# kelvin_ntc_B.net
KiCad netlist of a schematic drawn in EAGLE
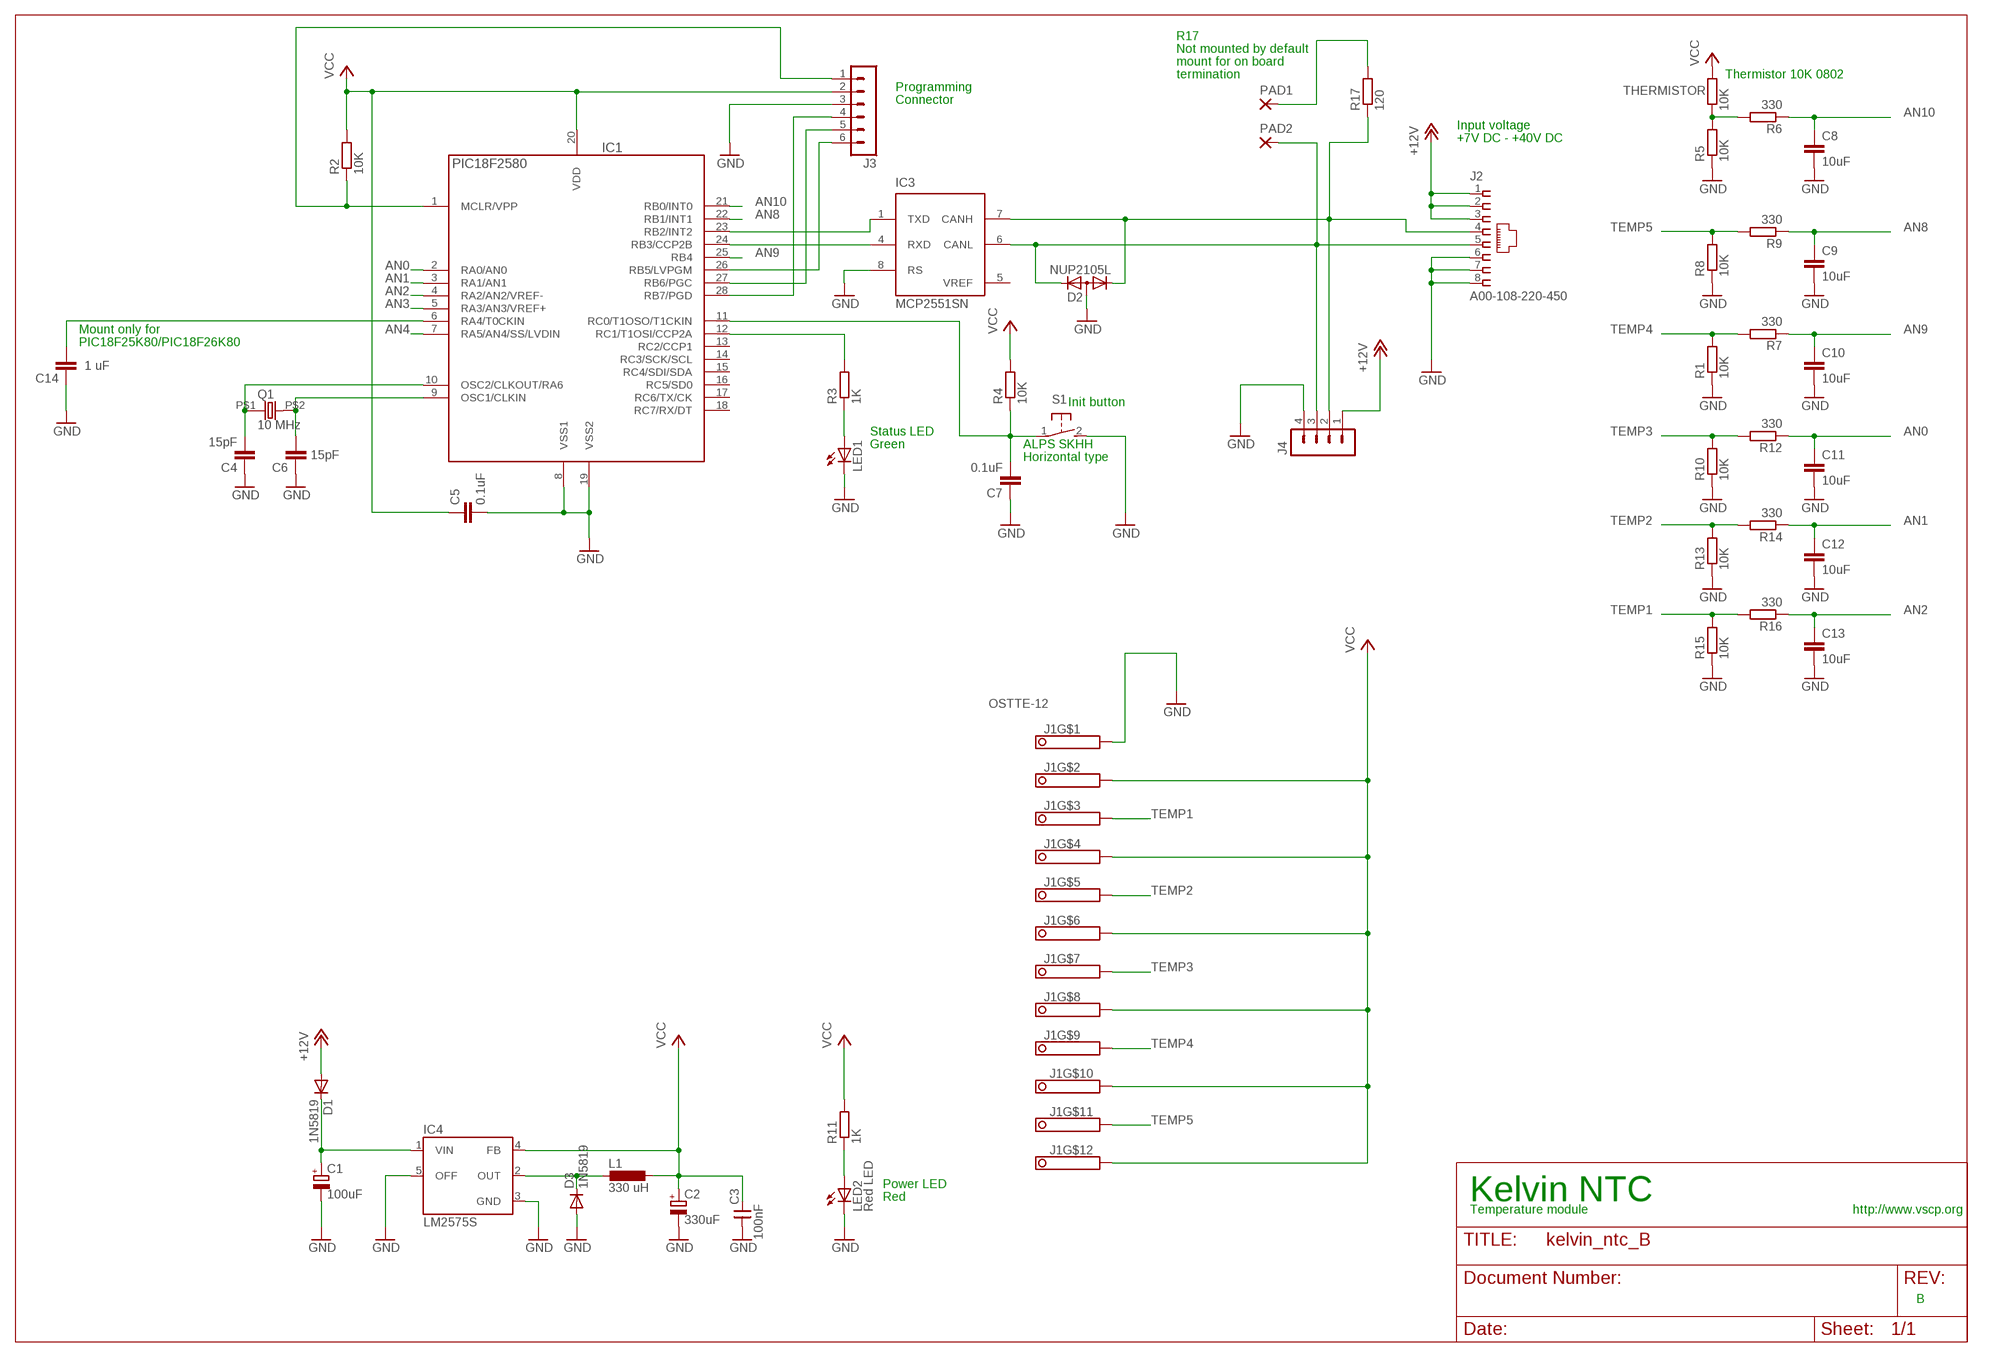
[diagram p0: schematic, sheet 1]

(export (version "E")
  (design (tool "Eeschema 10.0.6"))
  (components
    (comp (ref "C1")
      (value "100uF")
      (footprint "eagle-import:PANASONIC_D")
      (libsource (lib "eagle-import") (part "CPOL-EUD"))
    )
    (comp (ref "C2")
      (value "330uF")
      (footprint "eagle-import:PANASONIC_D")
      (libsource (lib "eagle-import") (part "CPOL-EUD"))
    )
    (comp (ref "C3")
      (value "100nF")
      (footprint "eagle-import:0805")
      (libsource (lib "eagle-import") (part "CNP-0805"))
    )
    (comp (ref "C4")
      (value "15pF")
      (footprint "eagle-import:C0805")
      (libsource (lib "eagle-import") (part "C-EUC0805"))
    )
    (comp (ref "C5")
      (value "0.1uF")
      (footprint "eagle-import:C0805")
      (libsource (lib "eagle-import") (part "C-EUC0805"))
    )
    (comp (ref "C6")
      (value "15pF")
      (footprint "eagle-import:C0805")
      (libsource (lib "eagle-import") (part "C-EUC0805"))
    )
    (comp (ref "C7")
      (value "0.1uF")
      (footprint "eagle-import:C0805")
      (libsource (lib "eagle-import") (part "C-EUC0805"))
    )
    (comp (ref "C8")
      (value "10uF")
      (footprint "eagle-import:C0805")
      (libsource (lib "eagle-import") (part "C-EUC0805"))
    )
    (comp (ref "C9")
      (value "10uF")
      (footprint "eagle-import:C0805")
      (libsource (lib "eagle-import") (part "C-EUC0805"))
    )
    (comp (ref "C10")
      (value "10uF")
      (footprint "eagle-import:C0805")
      (libsource (lib "eagle-import") (part "C-EUC0805"))
    )
    (comp (ref "C11")
      (value "10uF")
      (footprint "eagle-import:C0805")
      (libsource (lib "eagle-import") (part "C-EUC0805"))
    )
    (comp (ref "C12")
      (value "10uF")
      (footprint "eagle-import:C0805")
      (libsource (lib "eagle-import") (part "C-EUC0805"))
    )
    (comp (ref "C13")
      (value "10uF")
      (footprint "eagle-import:C0805")
      (libsource (lib "eagle-import") (part "C-EUC0805"))
    )
    (comp (ref "C14")
      (value "1 uF")
      (footprint "eagle-import:C0805")
      (libsource (lib "eagle-import") (part "C-EUC0805"))
    )
    (comp (ref "D1")
      (value "1N5819")
      (footprint "eagle-import:SOD123")
      (libsource (lib "eagle-import") (part "DIODE-SOD123"))
    )
    (comp (ref "D2")
      (value "NUP2105L")
      (footprint "eagle-import:SOT23")
      (libsource (lib "eagle-import") (part "DIODE-2CA|ACSOT23"))
    )
    (comp (ref "D3")
      (value "1N5819")
      (footprint "eagle-import:SOD123")
      (libsource (lib "eagle-import") (part "DIODE-SOD123"))
    )
    (comp (ref "IC1")
      (value "PIC18F2580")
      (footprint "eagle-import:SO28")
      (libsource (lib "eagle-import") (part "PIC18F252-?I/SOL"))
    )
    (comp (ref "IC3")
      (value "MCP2551SN")
      (footprint "eagle-import:SO-08")
      (libsource (lib "eagle-import") (part "MCP2551SN"))
    )
    (comp (ref "IC4")
      (value "LM2575S")
      (footprint "eagle-import:TO263-5")
      (libsource (lib "eagle-import") (part "LM2575S"))
    )
    (comp (ref "J1")
      (value "OSTTE-12")
      (footprint "eagle-import:PINHEAD-12")
      (libsource (lib "eagle-import") (part "OSTTE-12"))
    )
    (comp (ref "J2")
      (value "A00-108-220-450")
      (footprint "eagle-import:RJ-45")
      (libsource (lib "eagle-import") (part "A00-108-220-450"))
    )
    (comp (ref "J3")
      (value "MA06-1")
      (footprint "eagle-import:MA06-1")
      (libsource (lib "eagle-import") (part "MA06-1"))
    )
    (comp (ref "J4")
      (value "MA04-1")
      (footprint "eagle-import:MA04-1")
      (libsource (lib "eagle-import") (part "MA04-1"))
    )
    (comp (ref "L1")
      (value "330 uH")
      (footprint "eagle-import:DO3316P")
      (libsource (lib "eagle-import") (part "DO3316P"))
    )
    (comp (ref "LED1")
      (value "LEDCHIP-LED0805")
      (footprint "eagle-import:CHIP-LED0805")
      (libsource (lib "eagle-import") (part "LEDCHIP-LED0805"))
    )
    (comp (ref "LED2")
      (value "Red LED")
      (footprint "eagle-import:CHIP-LED0805")
      (libsource (lib "eagle-import") (part "LEDCHIP-LED0805"))
    )
    (comp (ref "PAD1")
      (value "1,6/0,8")
      (footprint "eagle-import:1,6_0,8")
      (libsource (lib "eagle-import") (part "1,6/0,8"))
    )
    (comp (ref "PAD2")
      (value "1,6/0,8")
      (footprint "eagle-import:1,6_0,8")
      (libsource (lib "eagle-import") (part "1,6/0,8"))
    )
    (comp (ref "Q1")
      (value "10 MHz")
      (footprint "eagle-import:9C")
      (libsource (lib "eagle-import") (part "HC-49S"))
    )
    (comp (ref "R1")
      (value "10K")
      (footprint "eagle-import:R0805")
      (libsource (lib "eagle-import") (part "R-EU_R0805"))
    )
    (comp (ref "R2")
      (value "10K")
      (footprint "eagle-import:R0805")
      (libsource (lib "eagle-import") (part "R-EU_R0805"))
    )
    (comp (ref "R3")
      (value "1K")
      (footprint "eagle-import:R0805")
      (libsource (lib "eagle-import") (part "R-EU_R0805"))
    )
    (comp (ref "R4")
      (value "10K")
      (footprint "eagle-import:R0805")
      (libsource (lib "eagle-import") (part "R-EU_R0805"))
    )
    (comp (ref "R5")
      (value "10K")
      (footprint "eagle-import:R0805")
      (libsource (lib "eagle-import") (part "R-EU_R0805"))
    )
    (comp (ref "R6")
      (value "330")
      (footprint "eagle-import:R0805")
      (libsource (lib "eagle-import") (part "R-EU_R0805"))
    )
    (comp (ref "R7")
      (value "330")
      (footprint "eagle-import:R0805")
      (libsource (lib "eagle-import") (part "R-EU_R0805"))
    )
    (comp (ref "R8")
      (value "10K")
      (footprint "eagle-import:R0805")
      (libsource (lib "eagle-import") (part "R-EU_R0805"))
    )
    (comp (ref "R9")
      (value "330")
      (footprint "eagle-import:R0805")
      (libsource (lib "eagle-import") (part "R-EU_R0805"))
    )
    (comp (ref "R10")
      (value "10K")
      (footprint "eagle-import:R0805")
      (libsource (lib "eagle-import") (part "R-EU_R0805"))
    )
    (comp (ref "R11")
      (value "1K")
      (footprint "eagle-import:R0805")
      (libsource (lib "eagle-import") (part "R-EU_R0805"))
    )
    (comp (ref "R12")
      (value "330")
      (footprint "eagle-import:R0805")
      (libsource (lib "eagle-import") (part "R-EU_R0805"))
    )
    (comp (ref "R13")
      (value "10K")
      (footprint "eagle-import:R0805")
      (libsource (lib "eagle-import") (part "R-EU_R0805"))
    )
    (comp (ref "R14")
      (value "330")
      (footprint "eagle-import:R0805")
      (libsource (lib "eagle-import") (part "R-EU_R0805"))
    )
    (comp (ref "R15")
      (value "10K")
      (footprint "eagle-import:R0805")
      (libsource (lib "eagle-import") (part "R-EU_R0805"))
    )
    (comp (ref "R16")
      (value "330")
      (footprint "eagle-import:R0805")
      (libsource (lib "eagle-import") (part "R-EU_R0805"))
    )
    (comp (ref "R17")
      (value "120")
      (footprint "eagle-import:R0805")
      (libsource (lib "eagle-import") (part "R-EU_R0805"))
    )
    (comp (ref "S1")
      (value "31-XX")
      (footprint "eagle-import:B3F-31XX")
      (fields (field (name "MPN") "B3F-3100"))
      (libsource (lib "eagle-import") (part "31-XX"))
    )
    (comp (ref "THERMISTOR")
      (value "10K")
      (footprint "eagle-import:R0805")
      (libsource (lib "eagle-import") (part "R-EU_R0805"))
    )
  )
  (nets
    (net (code "1") (name "+12V") (class "Default")
      (node (ref "D1") (pin "A") (pinfunction "A_A") (pintype "passive"))
      (node (ref "J2") (pin "1") (pinfunction "1_1") (pintype "passive"))
      (node (ref "J2") (pin "2") (pinfunction "2_2") (pintype "passive"))
      (node (ref "J2") (pin "3") (pinfunction "3_3") (pintype "passive"))
      (node (ref "J4") (pin "1") (pinfunction "1_1") (pintype "passive"))
    )
    (net (code "2") (name "/AN0") (class "Default")
      (node (ref "C11") (pin "1") (pinfunction "1_1") (pintype "passive"))
      (node (ref "IC1") (pin "2") (pinfunction "RA0/AN0_2") (pintype "bidirectional"))
      (node (ref "R12") (pin "1") (pinfunction "1_1") (pintype "passive"))
    )
    (net (code "3") (name "/AN1") (class "Default")
      (node (ref "C12") (pin "1") (pinfunction "1_1") (pintype "passive"))
      (node (ref "IC1") (pin "3") (pinfunction "RA1/AN1_3") (pintype "bidirectional"))
      (node (ref "R14") (pin "1") (pinfunction "1_1") (pintype "passive"))
    )
    (net (code "4") (name "/AN2") (class "Default")
      (node (ref "C13") (pin "1") (pinfunction "1_1") (pintype "passive"))
      (node (ref "IC1") (pin "4") (pinfunction "RA2/AN2/VREF-_4") (pintype "bidirectional"))
      (node (ref "R16") (pin "1") (pinfunction "1_1") (pintype "passive"))
    )
    (net (code "5") (name "/AN3") (class "Default")
      (node (ref "IC1") (pin "5") (pinfunction "RA3/AN3/VREF+_5") (pintype "bidirectional"))
    )
    (net (code "6") (name "/AN4") (class "Default")
      (node (ref "IC1") (pin "7") (pinfunction "RA5/AN4/SS/LVDIN_7") (pintype "bidirectional"))
    )
    (net (code "7") (name "/AN8") (class "Default")
      (node (ref "C9") (pin "1") (pinfunction "1_1") (pintype "passive"))
      (node (ref "IC1") (pin "22") (pinfunction "RB1/INT1_22") (pintype "bidirectional"))
      (node (ref "R9") (pin "1") (pinfunction "1_1") (pintype "passive"))
    )
    (net (code "8") (name "/AN9") (class "Default")
      (node (ref "C10") (pin "1") (pinfunction "1_1") (pintype "passive"))
      (node (ref "IC1") (pin "25") (pinfunction "RB4_25") (pintype "bidirectional"))
      (node (ref "R7") (pin "1") (pinfunction "1_1") (pintype "passive"))
    )
    (net (code "9") (name "/AN10") (class "Default")
      (node (ref "C8") (pin "1") (pinfunction "1_1") (pintype "passive"))
      (node (ref "IC1") (pin "21") (pinfunction "RB0/INT0_21") (pintype "bidirectional"))
      (node (ref "R6") (pin "1") (pinfunction "1_1") (pintype "passive"))
    )
    (net (code "10") (name "/TEMP1") (class "Default")
      (node (ref "J1") (pin "3") (pinfunction "K_3") (pintype "passive"))
      (node (ref "R15") (pin "2") (pinfunction "2_2") (pintype "passive"))
      (node (ref "R16") (pin "2") (pinfunction "2_2") (pintype "passive"))
    )
    (net (code "11") (name "/TEMP2") (class "Default")
      (node (ref "J1") (pin "5") (pinfunction "K_5") (pintype "passive"))
      (node (ref "R13") (pin "2") (pinfunction "2_2") (pintype "passive"))
      (node (ref "R14") (pin "2") (pinfunction "2_2") (pintype "passive"))
    )
    (net (code "12") (name "/TEMP3") (class "Default")
      (node (ref "J1") (pin "7") (pinfunction "K_7") (pintype "passive"))
      (node (ref "R10") (pin "2") (pinfunction "2_2") (pintype "passive"))
      (node (ref "R12") (pin "2") (pinfunction "2_2") (pintype "passive"))
    )
    (net (code "13") (name "/TEMP4") (class "Default")
      (node (ref "J1") (pin "9") (pinfunction "K_9") (pintype "passive"))
      (node (ref "R1") (pin "2") (pinfunction "2_2") (pintype "passive"))
      (node (ref "R7") (pin "2") (pinfunction "2_2") (pintype "passive"))
    )
    (net (code "14") (name "/TEMP5") (class "Default")
      (node (ref "J1") (pin "11") (pinfunction "K_11") (pintype "passive"))
      (node (ref "R8") (pin "2") (pinfunction "2_2") (pintype "passive"))
      (node (ref "R9") (pin "2") (pinfunction "2_2") (pintype "passive"))
    )
    (net (code "15") (name "/VREF") (class "Default")
      (node (ref "IC3") (pin "5") (pinfunction "VREF_5") (pintype "power_in"))
    )
    (net (code "16") (name "GND") (class "Default")
      (node (ref "C1") (pin "-") (pinfunction "-_-") (pintype "passive"))
      (node (ref "C10") (pin "2") (pinfunction "2_2") (pintype "passive"))
      (node (ref "C11") (pin "2") (pinfunction "2_2") (pintype "passive"))
      (node (ref "C12") (pin "2") (pinfunction "2_2") (pintype "passive"))
      (node (ref "C13") (pin "2") (pinfunction "2_2") (pintype "passive"))
      (node (ref "C14") (pin "1") (pinfunction "1_1") (pintype "passive"))
      (node (ref "C2") (pin "-") (pinfunction "-_-") (pintype "passive"))
      (node (ref "C3") (pin "1") (pinfunction "1_1") (pintype "passive"))
      (node (ref "C4") (pin "1") (pinfunction "1_1") (pintype "passive"))
      (node (ref "C5") (pin "2") (pinfunction "2_2") (pintype "passive"))
      (node (ref "C6") (pin "1") (pinfunction "1_1") (pintype "passive"))
      (node (ref "C7") (pin "1") (pinfunction "1_1") (pintype "passive"))
      (node (ref "C8") (pin "2") (pinfunction "2_2") (pintype "passive"))
      (node (ref "C9") (pin "2") (pinfunction "2_2") (pintype "passive"))
      (node (ref "D2") (pin "3") (pinfunction "A_3") (pintype "passive"))
      (node (ref "D3") (pin "A") (pinfunction "A_A") (pintype "passive"))
      (node (ref "IC1") (pin "19") (pinfunction "VSS2_19") (pintype "power_in"))
      (node (ref "IC1") (pin "8") (pinfunction "VSS1_8") (pintype "power_in"))
      (node (ref "IC3") (pin "8") (pinfunction "RS_8") (pintype "input"))
      (node (ref "IC4") (pin "3") (pinfunction "GND_3") (pintype "power_in"))
      (node (ref "IC4") (pin "5") (pinfunction "OFF_5") (pintype "input"))
      (node (ref "J1") (pin "1") (pinfunction "K_1") (pintype "passive"))
      (node (ref "J2") (pin "6") (pinfunction "6_6") (pintype "passive"))
      (node (ref "J2") (pin "7") (pinfunction "7_7") (pintype "passive"))
      (node (ref "J2") (pin "8") (pinfunction "8_8") (pintype "passive"))
      (node (ref "J3") (pin "3") (pinfunction "3_3") (pintype "passive"))
      (node (ref "J4") (pin "4") (pinfunction "4_4") (pintype "passive"))
      (node (ref "LED1") (pin "C") (pinfunction "C_C") (pintype "passive"))
      (node (ref "LED2") (pin "C") (pinfunction "C_C") (pintype "passive"))
      (node (ref "R1") (pin "1") (pinfunction "1_1") (pintype "passive"))
      (node (ref "R10") (pin "1") (pinfunction "1_1") (pintype "passive"))
      (node (ref "R13") (pin "1") (pinfunction "1_1") (pintype "passive"))
      (node (ref "R15") (pin "1") (pinfunction "1_1") (pintype "passive"))
      (node (ref "R5") (pin "1") (pinfunction "1_1") (pintype "passive"))
      (node (ref "R8") (pin "1") (pinfunction "1_1") (pintype "passive"))
      (node (ref "S1") (pin "2") (pinfunction "S_2") (pintype "passive"))
    )
    (net (code "17") (name "Net-(D2-K1)") (class "Default")
      (node (ref "D2") (pin "1") (pinfunction "K1_1") (pintype "passive"))
      (node (ref "IC3") (pin "7") (pinfunction "CANH_7") (pintype "bidirectional"))
      (node (ref "J2") (pin "4") (pinfunction "4_4") (pintype "passive"))
      (node (ref "J4") (pin "2") (pinfunction "2_2") (pintype "passive"))
      (node (ref "R17") (pin "1") (pinfunction "1_1") (pintype "passive"))
    )
    (net (code "18") (name "Net-(D2-K2)") (class "Default")
      (node (ref "D2") (pin "2") (pinfunction "K2_2") (pintype "passive"))
      (node (ref "IC3") (pin "6") (pinfunction "CANL_6") (pintype "bidirectional"))
      (node (ref "J2") (pin "5") (pinfunction "5_5") (pintype "passive"))
      (node (ref "J4") (pin "3") (pinfunction "3_3") (pintype "passive"))
      (node (ref "PAD2") (pin "1") (pinfunction "P_1") (pintype "passive"))
    )
    (net (code "19") (name "Net-(IC1-MCLR{slash}VPP)") (class "Default")
      (node (ref "IC1") (pin "1") (pinfunction "MCLR/VPP_1") (pintype "input"))
      (node (ref "J3") (pin "1") (pinfunction "1_1") (pintype "passive"))
      (node (ref "R2") (pin "1") (pinfunction "1_1") (pintype "passive"))
    )
    (net (code "20") (name "Net-(IC1-OSC1{slash}CLKIN)") (class "Default")
      (node (ref "C6") (pin "2") (pinfunction "2_2") (pintype "passive"))
      (node (ref "IC1") (pin "9") (pinfunction "OSC1/CLKIN_9") (pintype "input"))
      (node (ref "Q1") (pin "P$2") (pinfunction "2_P$2") (pintype "passive"))
    )
    (net (code "21") (name "Net-(IC1-OSC2{slash}CLKOUT{slash}RA6)") (class "Default")
      (node (ref "C4") (pin "2") (pinfunction "2_2") (pintype "passive"))
      (node (ref "IC1") (pin "10") (pinfunction "OSC2/CLKOUT/RA6_10") (pintype "output"))
      (node (ref "Q1") (pin "P$1") (pinfunction "1_P$1") (pintype "passive"))
    )
    (net (code "22") (name "Net-(IC1-RA4{slash}T0CKIN)") (class "Default")
      (node (ref "C14") (pin "2") (pinfunction "2_2") (pintype "passive"))
      (node (ref "IC1") (pin "6") (pinfunction "RA4/T0CKIN_6") (pintype "open_collector"))
    )
    (net (code "23") (name "Net-(IC1-RB2{slash}INT2)") (class "Default")
      (node (ref "IC1") (pin "23") (pinfunction "RB2/INT2_23") (pintype "bidirectional"))
      (node (ref "IC3") (pin "1") (pinfunction "TXD_1") (pintype "input"))
    )
    (net (code "24") (name "Net-(IC1-RB3{slash}CCP2B)") (class "Default")
      (node (ref "IC1") (pin "24") (pinfunction "RB3/CCP2B_24") (pintype "bidirectional"))
      (node (ref "IC3") (pin "4") (pinfunction "RXD_4") (pintype "output"))
    )
    (net (code "25") (name "Net-(IC1-RB5{slash}LVPGM)") (class "Default")
      (node (ref "IC1") (pin "26") (pinfunction "RB5/LVPGM_26") (pintype "bidirectional"))
      (node (ref "J3") (pin "6") (pinfunction "6_6") (pintype "passive"))
    )
    (net (code "26") (name "Net-(IC1-RB6{slash}PGC)") (class "Default")
      (node (ref "IC1") (pin "27") (pinfunction "RB6/PGC_27") (pintype "bidirectional"))
      (node (ref "J3") (pin "5") (pinfunction "5_5") (pintype "passive"))
    )
    (net (code "27") (name "Net-(IC1-RB7{slash}PGD)") (class "Default")
      (node (ref "IC1") (pin "28") (pinfunction "RB7/PGD_28") (pintype "bidirectional"))
      (node (ref "J3") (pin "4") (pinfunction "4_4") (pintype "passive"))
    )
    (net (code "28") (name "Net-(IC1-RC0{slash}T1OSO{slash}T1CKIN)") (class "Default")
      (node (ref "C7") (pin "2") (pinfunction "2_2") (pintype "passive"))
      (node (ref "IC1") (pin "11") (pinfunction "RC0/T1OSO/T1CKIN_11") (pintype "bidirectional"))
      (node (ref "R4") (pin "1") (pinfunction "1_1") (pintype "passive"))
      (node (ref "S1") (pin "1") (pinfunction "P_1") (pintype "passive"))
    )
    (net (code "29") (name "Net-(IC1-RC1{slash}T1OSI{slash}CCP2A)") (class "Default")
      (node (ref "IC1") (pin "12") (pinfunction "RC1/T1OSI/CCP2A_12") (pintype "bidirectional"))
      (node (ref "R3") (pin "2") (pinfunction "2_2") (pintype "passive"))
    )
    (net (code "30") (name "Net-(IC4-OUT)") (class "Default")
      (node (ref "D3") (pin "C") (pinfunction "C_C") (pintype "passive"))
      (node (ref "IC4") (pin "2") (pinfunction "OUT_2") (pintype "output"))
      (node (ref "L1") (pin "1") (pinfunction "1_1") (pintype "passive"))
    )
    (net (code "31") (name "Net-(IC4-VIN)") (class "Default")
      (node (ref "C1") (pin "+") (pinfunction "+_+") (pintype "passive"))
      (node (ref "D1") (pin "C") (pinfunction "C_C") (pintype "passive"))
      (node (ref "IC4") (pin "1") (pinfunction "VIN_1") (pintype "power_in"))
    )
    (net (code "32") (name "Net-(LED1-PadA)") (class "Default")
      (node (ref "LED1") (pin "A") (pinfunction "A_A") (pintype "passive"))
      (node (ref "R3") (pin "1") (pinfunction "1_1") (pintype "passive"))
    )
    (net (code "33") (name "Net-(LED2-PadA)") (class "Default")
      (node (ref "LED2") (pin "A") (pinfunction "A_A") (pintype "passive"))
      (node (ref "R11") (pin "1") (pinfunction "1_1") (pintype "passive"))
    )
    (net (code "34") (name "Net-(PAD1-P)") (class "Default")
      (node (ref "PAD1") (pin "1") (pinfunction "P_1") (pintype "passive"))
      (node (ref "R17") (pin "2") (pinfunction "2_2") (pintype "passive"))
    )
    (net (code "35") (name "Net-(R5-Pad2)") (class "Default")
      (node (ref "R5") (pin "2") (pinfunction "2_2") (pintype "passive"))
      (node (ref "R6") (pin "2") (pinfunction "2_2") (pintype "passive"))
      (node (ref "THERMISTOR") (pin "1") (pinfunction "1_1") (pintype "passive"))
    )
    (net (code "36") (name "VCC") (class "Default")
      (node (ref "C2") (pin "+") (pinfunction "+_+") (pintype "passive"))
      (node (ref "C3") (pin "2") (pinfunction "2_2") (pintype "passive"))
      (node (ref "C5") (pin "1") (pinfunction "1_1") (pintype "passive"))
      (node (ref "IC1") (pin "20") (pinfunction "VDD_20") (pintype "power_in"))
      (node (ref "IC4") (pin "4") (pinfunction "FB_4") (pintype "input"))
      (node (ref "J1") (pin "10") (pinfunction "K_10") (pintype "passive"))
      (node (ref "J1") (pin "12") (pinfunction "K_12") (pintype "passive"))
      (node (ref "J1") (pin "2") (pinfunction "K_2") (pintype "passive"))
      (node (ref "J1") (pin "4") (pinfunction "K_4") (pintype "passive"))
      (node (ref "J1") (pin "6") (pinfunction "K_6") (pintype "passive"))
      (node (ref "J1") (pin "8") (pinfunction "K_8") (pintype "passive"))
      (node (ref "J3") (pin "2") (pinfunction "2_2") (pintype "passive"))
      (node (ref "L1") (pin "2") (pinfunction "2_2") (pintype "passive"))
      (node (ref "R11") (pin "2") (pinfunction "2_2") (pintype "passive"))
      (node (ref "R2") (pin "2") (pinfunction "2_2") (pintype "passive"))
      (node (ref "R4") (pin "2") (pinfunction "2_2") (pintype "passive"))
      (node (ref "THERMISTOR") (pin "2") (pinfunction "2_2") (pintype "passive"))
    )
    (net (code "37") (name "unconnected-(IC1-RC2{slash}CCP1-Pad13)") (class "Default")
      (node (ref "IC1") (pin "13") (pinfunction "RC2/CCP1_13") (pintype "bidirectional"))
    )
    (net (code "38") (name "unconnected-(IC1-RC3{slash}SCK{slash}SCL-Pad14)") (class "Default")
      (node (ref "IC1") (pin "14") (pinfunction "RC3/SCK/SCL_14") (pintype "bidirectional"))
    )
    (net (code "39") (name "unconnected-(IC1-RC4{slash}SDI{slash}SDA-Pad15)") (class "Default")
      (node (ref "IC1") (pin "15") (pinfunction "RC4/SDI/SDA_15") (pintype "bidirectional"))
    )
    (net (code "40") (name "unconnected-(IC1-RC5{slash}SD0-Pad16)") (class "Default")
      (node (ref "IC1") (pin "16") (pinfunction "RC5/SD0_16") (pintype "bidirectional"))
    )
    (net (code "41") (name "unconnected-(IC1-RC6{slash}TX{slash}CK-Pad17)") (class "Default")
      (node (ref "IC1") (pin "17") (pinfunction "RC6/TX/CK_17") (pintype "bidirectional"))
    )
    (net (code "42") (name "unconnected-(IC1-RC7{slash}RX{slash}DT-Pad18)") (class "Default")
      (node (ref "IC1") (pin "18") (pinfunction "RC7/RX/DT_18") (pintype "bidirectional"))
    )
  )
)
